# X14-Backplane.net
KiCad netlist of a schematic drawn in EAGLE
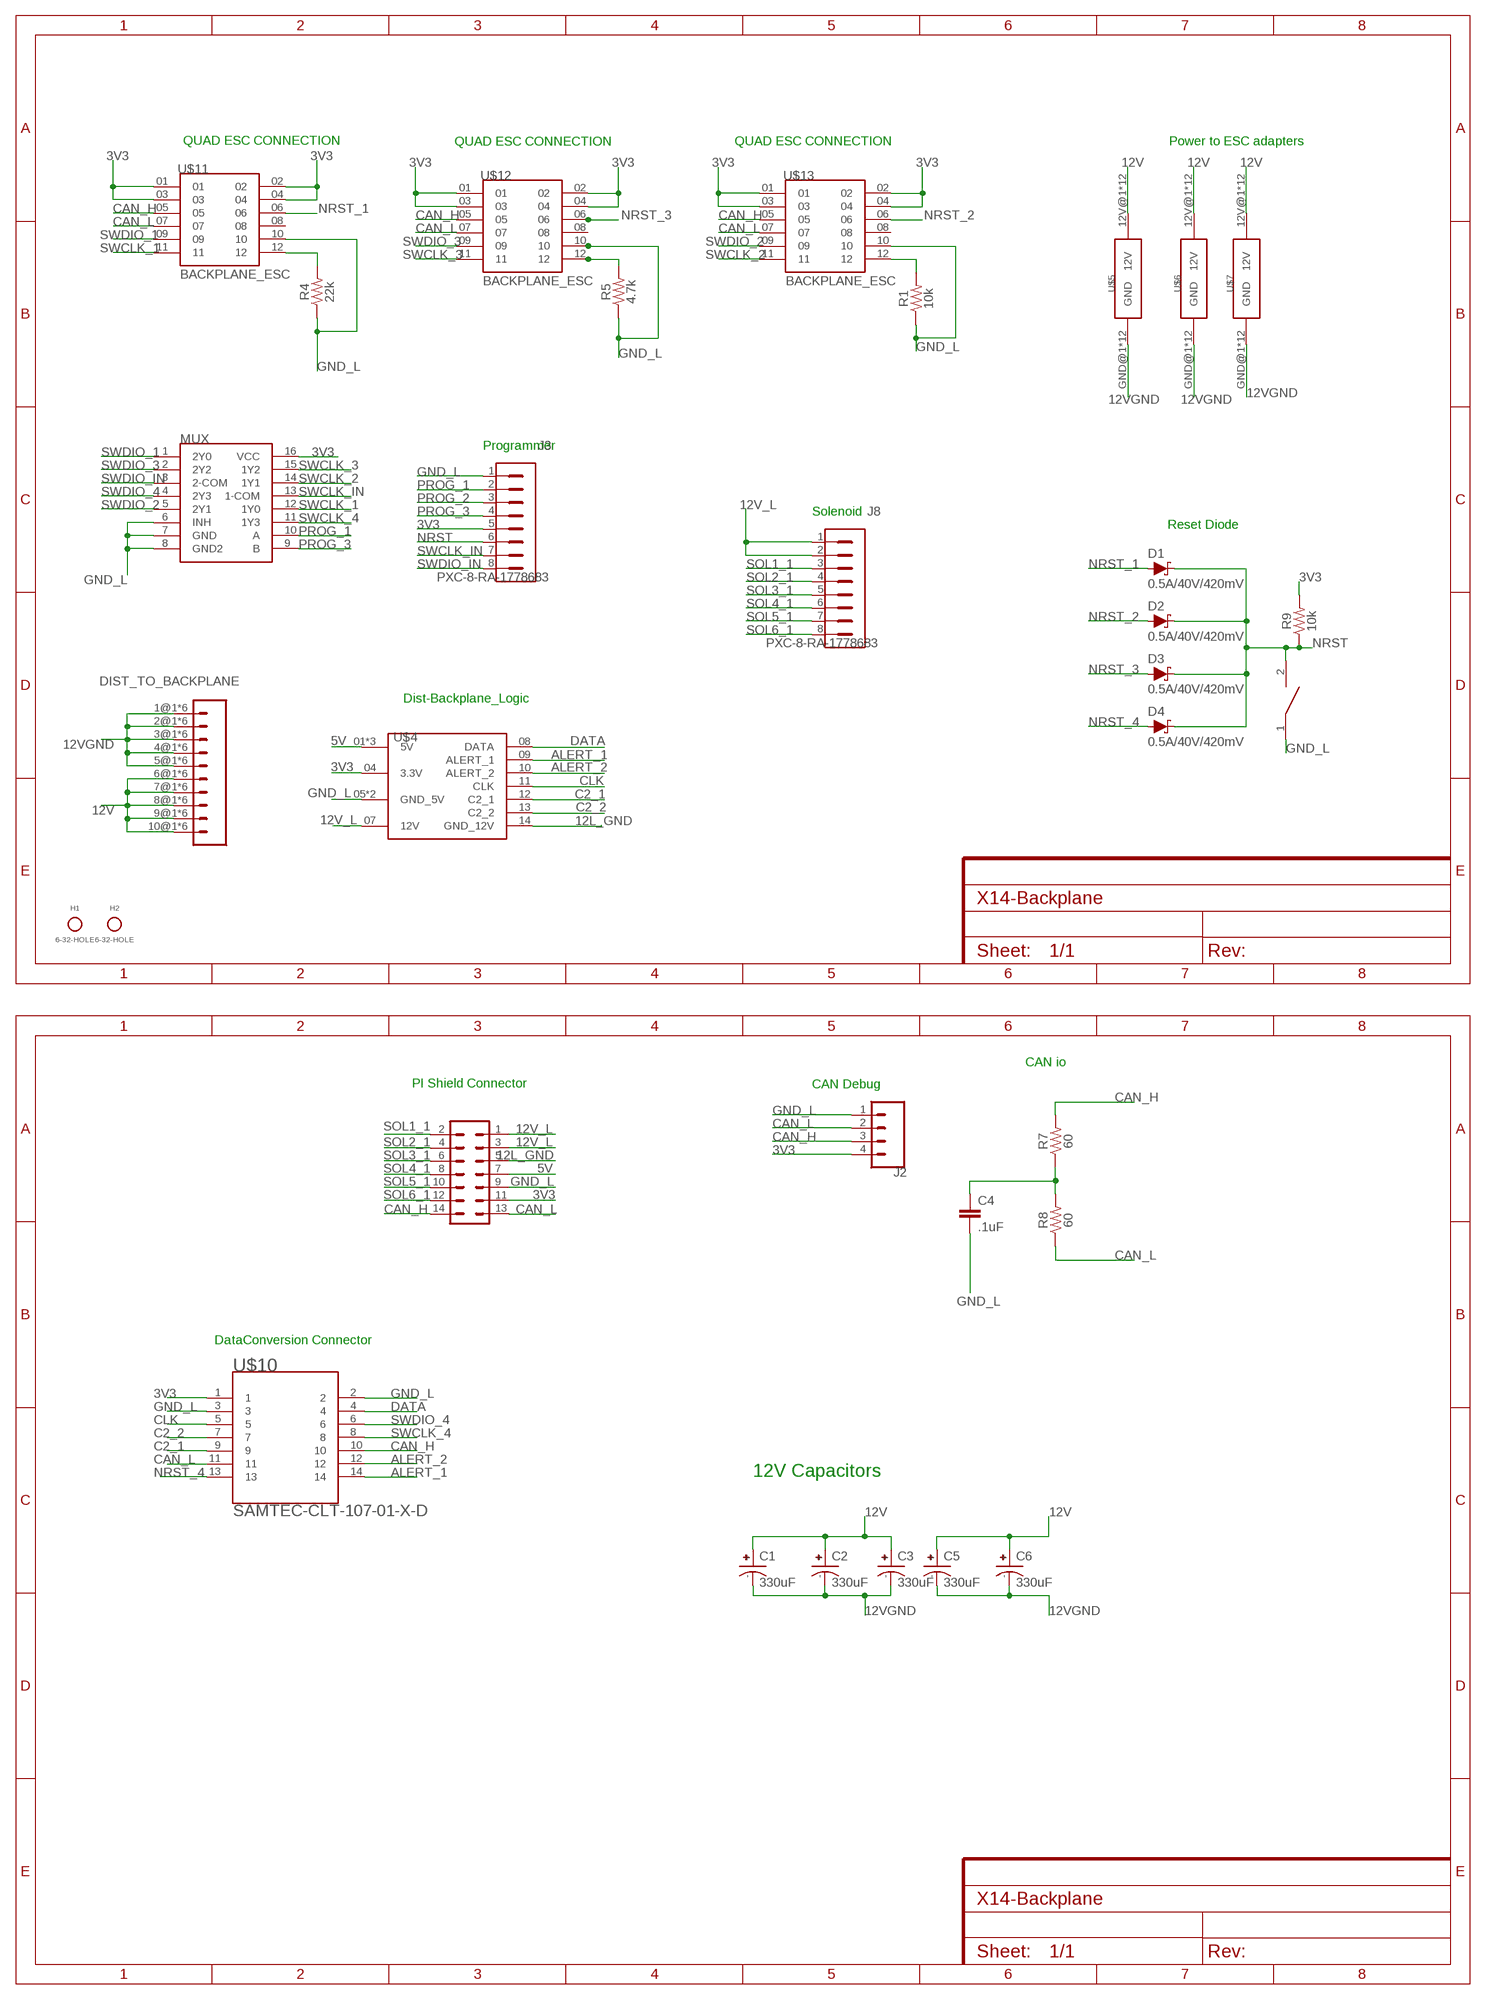
[diagram p0: schematic, sheet 1]

(export (version "E")
  (design (tool "Eeschema 10.0.6"))
  (components
    (comp (ref "C1")
      (value "330uF")
      (footprint "eagle-import:CAPAE1030X1050N")
      (fields
        (field (name "ARROW_PART_NUMBER") "UCM1H331MNL1GS")
        (field (name "MOUSER_PART_NUMBER") "647-UCM1H331MNL1GS")
      )
      (libsource (lib "eagle-import") (part "UCM1H331MNL1GS"))
    )
    (comp (ref "C2")
      (value "330uF")
      (footprint "eagle-import:CAPAE1030X1050N")
      (fields
        (field (name "ARROW_PART_NUMBER") "UCM1H331MNL1GS")
        (field (name "MOUSER_PART_NUMBER") "647-UCM1H331MNL1GS")
      )
      (libsource (lib "eagle-import") (part "UCM1H331MNL1GS"))
    )
    (comp (ref "C3")
      (value "330uF")
      (footprint "eagle-import:CAPAE1030X1050N")
      (fields
        (field (name "ARROW_PART_NUMBER") "UCM1H331MNL1GS")
        (field (name "MOUSER_PART_NUMBER") "647-UCM1H331MNL1GS")
      )
      (libsource (lib "eagle-import") (part "UCM1H331MNL1GS"))
    )
    (comp (ref "C4")
      (value ".1uF")
      (footprint "eagle-import:0603")
      (libsource (lib "eagle-import") (part "10NF-0603-50V-10%"))
    )
    (comp (ref "C5")
      (value "330uF")
      (footprint "eagle-import:CAPAE1030X1050N")
      (fields
        (field (name "ARROW_PART_NUMBER") "UCM1H331MNL1GS")
        (field (name "MOUSER_PART_NUMBER") "647-UCM1H331MNL1GS")
      )
      (libsource (lib "eagle-import") (part "UCM1H331MNL1GS"))
    )
    (comp (ref "C6")
      (value "330uF")
      (footprint "eagle-import:CAPAE1030X1050N")
      (fields
        (field (name "ARROW_PART_NUMBER") "UCM1H331MNL1GS")
        (field (name "MOUSER_PART_NUMBER") "647-UCM1H331MNL1GS")
      )
      (libsource (lib "eagle-import") (part "UCM1H331MNL1GS"))
    )
    (comp (ref "D1")
      (value "0.5A/40V/420mV")
      (footprint "eagle-import:SOD-323")
      (libsource (lib "eagle-import") (part "DIODE-SCHOTTKY-PMEG4005EJ"))
    )
    (comp (ref "D2")
      (value "0.5A/40V/420mV")
      (footprint "eagle-import:SOD-323")
      (libsource (lib "eagle-import") (part "DIODE-SCHOTTKY-PMEG4005EJ"))
    )
    (comp (ref "D3")
      (value "0.5A/40V/420mV")
      (footprint "eagle-import:SOD-323")
      (libsource (lib "eagle-import") (part "DIODE-SCHOTTKY-PMEG4005EJ"))
    )
    (comp (ref "D4")
      (value "0.5A/40V/420mV")
      (footprint "eagle-import:SOD-323")
      (libsource (lib "eagle-import") (part "DIODE-SCHOTTKY-PMEG4005EJ"))
    )
    (comp (ref "DIST_TO_BACKPLANE")
      (value "MPPT-10-01-01-L-RA-SD")
      (footprint "eagle-import:MPPT-10-01-01-L-RA-SD")
      (libsource (lib "eagle-import") (part "MPPT-10-01-01-L-RA-SD"))
    )
    (comp (ref "H1")
      (value "6-32-HOLE")
      (footprint "eagle-import:6-32-HOLE")
      (libsource (lib "eagle-import") (part "6-32-HOLE"))
    )
    (comp (ref "H2")
      (value "6-32-HOLE")
      (footprint "eagle-import:6-32-HOLE")
      (libsource (lib "eagle-import") (part "6-32-HOLE"))
    )
    (comp (ref "J2")
      (value "PXC-PTSM-04-RA-1778641")
      (footprint "eagle-import:PXC-PTSM-04-RA-1778641")
      (libsource (lib "eagle-import") (part "PXC-PTSM-04-RA-1778641"))
    )
    (comp (ref "J3")
      (value "PXC-8-RA-1778683")
      (footprint "eagle-import:PXC-8-RA-1778683")
      (libsource (lib "eagle-import") (part "PXC-8-RA-1778683"))
    )
    (comp (ref "J8")
      (value "PXC-8-RA-1778683")
      (footprint "eagle-import:PXC-8-RA-1778683")
      (libsource (lib "eagle-import") (part "PXC-8-RA-1778683"))
    )
    (comp (ref "MUX")
      (value "TI-SN74LV4052A")
      (footprint "eagle-import:SOIC-16")
      (libsource (lib "eagle-import") (part "TI-SN74LV4052A"))
    )
    (comp (ref "R1")
      (value "10k")
      (footprint "eagle-import:0603")
      (libsource (lib "eagle-import") (part "10KOHM-0603-1/10W-1%"))
    )
    (comp (ref "R4")
      (value "22k")
      (footprint "eagle-import:0603")
      (libsource (lib "eagle-import") (part "26.7KOHM0603-1/10W-1%"))
    )
    (comp (ref "R5")
      (value "4.7k")
      (footprint "eagle-import:0603")
      (libsource (lib "eagle-import") (part "1KOHM-0603-1/10W-1%"))
    )
    (comp (ref "R7")
      (value "60")
      (footprint "eagle-import:0603")
      (libsource (lib "eagle-import") (part "68.1KOHM-0603-1/10W-1%"))
    )
    (comp (ref "R8")
      (value "60")
      (footprint "eagle-import:0603")
      (libsource (lib "eagle-import") (part "68.1KOHM-0603-1/10W-1%"))
    )
    (comp (ref "R9")
      (value "10k")
      (footprint "eagle-import:0603")
      (libsource (lib "eagle-import") (part "10KOHM-0603-1/10W-1%"))
    )
    (comp (ref "U$4")
      (value "BACKPLANE-DISTRIBUTION")
      (footprint "eagle-import:SAMTEC_IPL1-107-01-X-D-K(B-D)")
      (libsource (lib "eagle-import") (part "BACKPLANE-DISTRIBUTION"))
    )
    (comp (ref "U$5")
      (value "BACKPLANE_ESC_ADAPTER_PWRBKP")
      (footprint "eagle-import:BACKPLANE_ESC_ADAPTER_BKP_PWR")
      (libsource (lib "eagle-import") (part "BACKPLANE_ESC_ADAPTER_PWRBKP"))
    )
    (comp (ref "U$6")
      (value "BACKPLANE_ESC_ADAPTER_PWRBKP")
      (footprint "eagle-import:BACKPLANE_ESC_ADAPTER_BKP_PWR")
      (libsource (lib "eagle-import") (part "BACKPLANE_ESC_ADAPTER_PWRBKP"))
    )
    (comp (ref "U$7")
      (value "BACKPLANE_ESC_ADAPTER_PWRBKP")
      (footprint "eagle-import:BACKPLANE_ESC_ADAPTER_BKP_PWR")
      (libsource (lib "eagle-import") (part "BACKPLANE_ESC_ADAPTER_PWRBKP"))
    )
    (comp (ref "U$8")
      (value "DISCRETECOMPONENTS_SWITCH")
      (footprint "eagle-import:DISCRETECOMPONENTS_SW_2512")
      (libsource (lib "eagle-import") (part "DISCRETECOMPONENTS_SWITCH"))
    )
    (comp (ref "U$9")
      (value "7X_CONN")
      (footprint "eagle-import:IPL7X2")
      (libsource (lib "eagle-import") (part "7X_CONN"))
    )
    (comp (ref "U$10")
      (value "BACKPLANE->DATACONV")
      (footprint "eagle-import:SAMTEC-CLT-107-01-X-D-BACKPLANE")
      (libsource (lib "eagle-import") (part "BACKPLANE-{gt}DATACONV"))
    )
    (comp (ref "U$11")
      (value "BACKPLANE_ESC")
      (footprint "eagle-import:SAMTEC_SQT-107-01-F-D")
      (libsource (lib "eagle-import") (part "BACKPLANE_ESC"))
    )
    (comp (ref "U$12")
      (value "BACKPLANE_ESC")
      (footprint "eagle-import:SAMTEC_SQT-107-01-F-D")
      (libsource (lib "eagle-import") (part "BACKPLANE_ESC"))
    )
    (comp (ref "U$13")
      (value "BACKPLANE_ESC")
      (footprint "eagle-import:SAMTEC_SQT-107-01-F-D")
      (libsource (lib "eagle-import") (part "BACKPLANE_ESC"))
    )
  )
  (nets
    (net (code "1") (name "/3V3") (class "Default")
      (node (ref "J2") (pin "4") (pinfunction "4_4") (pintype "passive"))
      (node (ref "J3") (pin "5") (pinfunction "5_5") (pintype "passive"))
      (node (ref "MUX") (pin "16") (pinfunction "VCC_16") (pintype "bidirectional"))
      (node (ref "R9") (pin "2") (pinfunction "2_2") (pintype "passive"))
      (node (ref "U$10") (pin "1") (pinfunction "1_1") (pintype "passive"))
      (node (ref "U$11") (pin "01") (pinfunction "01_01") (pintype "passive"))
      (node (ref "U$11") (pin "02") (pinfunction "02_02") (pintype "passive"))
      (node (ref "U$11") (pin "03") (pinfunction "03_03") (pintype "passive"))
      (node (ref "U$11") (pin "04") (pinfunction "04_04") (pintype "passive"))
      (node (ref "U$12") (pin "01") (pinfunction "01_01") (pintype "passive"))
      (node (ref "U$12") (pin "02") (pinfunction "02_02") (pintype "passive"))
      (node (ref "U$12") (pin "03") (pinfunction "03_03") (pintype "passive"))
      (node (ref "U$12") (pin "04") (pinfunction "04_04") (pintype "passive"))
      (node (ref "U$13") (pin "01") (pinfunction "01_01") (pintype "passive"))
      (node (ref "U$13") (pin "02") (pinfunction "02_02") (pintype "passive"))
      (node (ref "U$13") (pin "03") (pinfunction "03_03") (pintype "passive"))
      (node (ref "U$13") (pin "04") (pinfunction "04_04") (pintype "passive"))
      (node (ref "U$4") (pin "04") (pinfunction "3.3V_04") (pintype "passive"))
      (node (ref "U$9") (pin "11") (pinfunction "24_11") (pintype "passive"))
    )
    (net (code "2") (name "/5V") (class "Default")
      (node (ref "U$4") (pin "01") (pinfunction "5V_01") (pintype "passive"))
      (node (ref "U$4") (pin "02") (pinfunction "5V_02") (pintype "passive"))
      (node (ref "U$4") (pin "03") (pinfunction "5V_03") (pintype "passive"))
      (node (ref "U$9") (pin "7") (pinfunction "20_7") (pintype "passive"))
    )
    (net (code "3") (name "/12L_GND") (class "Default")
      (node (ref "U$4") (pin "14") (pinfunction "GND_12V_14") (pintype "passive"))
      (node (ref "U$9") (pin "5") (pinfunction "18_5") (pintype "passive"))
    )
    (net (code "4") (name "/12V") (class "Default")
      (node (ref "C1") (pin "+") (pinfunction "+_+") (pintype "bidirectional"))
      (node (ref "C2") (pin "+") (pinfunction "+_+") (pintype "bidirectional"))
      (node (ref "C3") (pin "+") (pinfunction "+_+") (pintype "bidirectional"))
      (node (ref "C5") (pin "+") (pinfunction "+_+") (pintype "bidirectional"))
      (node (ref "C6") (pin "+") (pinfunction "+_+") (pintype "bidirectional"))
      (node (ref "DIST_TO_BACKPLANE") (pin "10@1") (pinfunction "10_10@1") (pintype "passive"))
      (node (ref "DIST_TO_BACKPLANE") (pin "10@2") (pinfunction "10_10@2") (pintype "passive"))
      (node (ref "DIST_TO_BACKPLANE") (pin "10@3") (pinfunction "10_10@3") (pintype "passive"))
      (node (ref "DIST_TO_BACKPLANE") (pin "10@4") (pinfunction "10_10@4") (pintype "passive"))
      (node (ref "DIST_TO_BACKPLANE") (pin "10@5") (pinfunction "10_10@5") (pintype "passive"))
      (node (ref "DIST_TO_BACKPLANE") (pin "10@6") (pinfunction "10_10@6") (pintype "passive"))
      (node (ref "DIST_TO_BACKPLANE") (pin "6@1") (pinfunction "6_6@1") (pintype "passive"))
      (node (ref "DIST_TO_BACKPLANE") (pin "6@2") (pinfunction "6_6@2") (pintype "passive"))
      (node (ref "DIST_TO_BACKPLANE") (pin "6@3") (pinfunction "6_6@3") (pintype "passive"))
      (node (ref "DIST_TO_BACKPLANE") (pin "6@4") (pinfunction "6_6@4") (pintype "passive"))
      (node (ref "DIST_TO_BACKPLANE") (pin "6@5") (pinfunction "6_6@5") (pintype "passive"))
      (node (ref "DIST_TO_BACKPLANE") (pin "6@6") (pinfunction "6_6@6") (pintype "passive"))
      (node (ref "DIST_TO_BACKPLANE") (pin "7@1") (pinfunction "7_7@1") (pintype "passive"))
      (node (ref "DIST_TO_BACKPLANE") (pin "7@2") (pinfunction "7_7@2") (pintype "passive"))
      (node (ref "DIST_TO_BACKPLANE") (pin "7@3") (pinfunction "7_7@3") (pintype "passive"))
      (node (ref "DIST_TO_BACKPLANE") (pin "7@4") (pinfunction "7_7@4") (pintype "passive"))
      (node (ref "DIST_TO_BACKPLANE") (pin "7@5") (pinfunction "7_7@5") (pintype "passive"))
      (node (ref "DIST_TO_BACKPLANE") (pin "7@6") (pinfunction "7_7@6") (pintype "passive"))
      (node (ref "DIST_TO_BACKPLANE") (pin "8@1") (pinfunction "8_8@1") (pintype "passive"))
      (node (ref "DIST_TO_BACKPLANE") (pin "8@2") (pinfunction "8_8@2") (pintype "passive"))
      (node (ref "DIST_TO_BACKPLANE") (pin "8@3") (pinfunction "8_8@3") (pintype "passive"))
      (node (ref "DIST_TO_BACKPLANE") (pin "8@4") (pinfunction "8_8@4") (pintype "passive"))
      (node (ref "DIST_TO_BACKPLANE") (pin "8@5") (pinfunction "8_8@5") (pintype "passive"))
      (node (ref "DIST_TO_BACKPLANE") (pin "8@6") (pinfunction "8_8@6") (pintype "passive"))
      (node (ref "DIST_TO_BACKPLANE") (pin "9@1") (pinfunction "9_9@1") (pintype "passive"))
      (node (ref "DIST_TO_BACKPLANE") (pin "9@2") (pinfunction "9_9@2") (pintype "passive"))
      (node (ref "DIST_TO_BACKPLANE") (pin "9@3") (pinfunction "9_9@3") (pintype "passive"))
      (node (ref "DIST_TO_BACKPLANE") (pin "9@4") (pinfunction "9_9@4") (pintype "passive"))
      (node (ref "DIST_TO_BACKPLANE") (pin "9@5") (pinfunction "9_9@5") (pintype "passive"))
      (node (ref "DIST_TO_BACKPLANE") (pin "9@6") (pinfunction "9_9@6") (pintype "passive"))
      (node (ref "U$5") (pin "12V@1") (pinfunction "12V_12V@1") (pintype "bidirectional"))
      (node (ref "U$5") (pin "12V@10") (pinfunction "12V_12V@10") (pintype "bidirectional"))
      (node (ref "U$5") (pin "12V@11") (pinfunction "12V_12V@11") (pintype "bidirectional"))
      (node (ref "U$5") (pin "12V@12") (pinfunction "12V_12V@12") (pintype "bidirectional"))
      (node (ref "U$5") (pin "12V@2") (pinfunction "12V_12V@2") (pintype "bidirectional"))
      (node (ref "U$5") (pin "12V@3") (pinfunction "12V_12V@3") (pintype "bidirectional"))
      (node (ref "U$5") (pin "12V@4") (pinfunction "12V_12V@4") (pintype "bidirectional"))
      (node (ref "U$5") (pin "12V@5") (pinfunction "12V_12V@5") (pintype "bidirectional"))
      (node (ref "U$5") (pin "12V@6") (pinfunction "12V_12V@6") (pintype "bidirectional"))
      (node (ref "U$5") (pin "12V@7") (pinfunction "12V_12V@7") (pintype "bidirectional"))
      (node (ref "U$5") (pin "12V@8") (pinfunction "12V_12V@8") (pintype "bidirectional"))
      (node (ref "U$5") (pin "12V@9") (pinfunction "12V_12V@9") (pintype "bidirectional"))
      (node (ref "U$6") (pin "12V@1") (pinfunction "12V_12V@1") (pintype "bidirectional"))
      (node (ref "U$6") (pin "12V@10") (pinfunction "12V_12V@10") (pintype "bidirectional"))
      (node (ref "U$6") (pin "12V@11") (pinfunction "12V_12V@11") (pintype "bidirectional"))
      (node (ref "U$6") (pin "12V@12") (pinfunction "12V_12V@12") (pintype "bidirectional"))
      (node (ref "U$6") (pin "12V@2") (pinfunction "12V_12V@2") (pintype "bidirectional"))
      (node (ref "U$6") (pin "12V@3") (pinfunction "12V_12V@3") (pintype "bidirectional"))
      (node (ref "U$6") (pin "12V@4") (pinfunction "12V_12V@4") (pintype "bidirectional"))
      (node (ref "U$6") (pin "12V@5") (pinfunction "12V_12V@5") (pintype "bidirectional"))
      (node (ref "U$6") (pin "12V@6") (pinfunction "12V_12V@6") (pintype "bidirectional"))
      (node (ref "U$6") (pin "12V@7") (pinfunction "12V_12V@7") (pintype "bidirectional"))
      (node (ref "U$6") (pin "12V@8") (pinfunction "12V_12V@8") (pintype "bidirectional"))
      (node (ref "U$6") (pin "12V@9") (pinfunction "12V_12V@9") (pintype "bidirectional"))
      (node (ref "U$7") (pin "12V@1") (pinfunction "12V_12V@1") (pintype "bidirectional"))
      (node (ref "U$7") (pin "12V@10") (pinfunction "12V_12V@10") (pintype "bidirectional"))
      (node (ref "U$7") (pin "12V@11") (pinfunction "12V_12V@11") (pintype "bidirectional"))
      (node (ref "U$7") (pin "12V@12") (pinfunction "12V_12V@12") (pintype "bidirectional"))
      (node (ref "U$7") (pin "12V@2") (pinfunction "12V_12V@2") (pintype "bidirectional"))
      (node (ref "U$7") (pin "12V@3") (pinfunction "12V_12V@3") (pintype "bidirectional"))
      (node (ref "U$7") (pin "12V@4") (pinfunction "12V_12V@4") (pintype "bidirectional"))
      (node (ref "U$7") (pin "12V@5") (pinfunction "12V_12V@5") (pintype "bidirectional"))
      (node (ref "U$7") (pin "12V@6") (pinfunction "12V_12V@6") (pintype "bidirectional"))
      (node (ref "U$7") (pin "12V@7") (pinfunction "12V_12V@7") (pintype "bidirectional"))
      (node (ref "U$7") (pin "12V@8") (pinfunction "12V_12V@8") (pintype "bidirectional"))
      (node (ref "U$7") (pin "12V@9") (pinfunction "12V_12V@9") (pintype "bidirectional"))
    )
    (net (code "5") (name "/12VGND") (class "Default")
      (node (ref "C1") (pin "-") (pinfunction "-_-") (pintype "bidirectional"))
      (node (ref "C2") (pin "-") (pinfunction "-_-") (pintype "bidirectional"))
      (node (ref "C3") (pin "-") (pinfunction "-_-") (pintype "bidirectional"))
      (node (ref "C5") (pin "-") (pinfunction "-_-") (pintype "bidirectional"))
      (node (ref "C6") (pin "-") (pinfunction "-_-") (pintype "bidirectional"))
      (node (ref "DIST_TO_BACKPLANE") (pin "1@1") (pinfunction "1_1@1") (pintype "passive"))
      (node (ref "DIST_TO_BACKPLANE") (pin "1@2") (pinfunction "1_1@2") (pintype "passive"))
      (node (ref "DIST_TO_BACKPLANE") (pin "1@3") (pinfunction "1_1@3") (pintype "passive"))
      (node (ref "DIST_TO_BACKPLANE") (pin "1@4") (pinfunction "1_1@4") (pintype "passive"))
      (node (ref "DIST_TO_BACKPLANE") (pin "1@5") (pinfunction "1_1@5") (pintype "passive"))
      (node (ref "DIST_TO_BACKPLANE") (pin "1@6") (pinfunction "1_1@6") (pintype "passive"))
      (node (ref "DIST_TO_BACKPLANE") (pin "2@1") (pinfunction "2_2@1") (pintype "passive"))
      (node (ref "DIST_TO_BACKPLANE") (pin "2@2") (pinfunction "2_2@2") (pintype "passive"))
      (node (ref "DIST_TO_BACKPLANE") (pin "2@3") (pinfunction "2_2@3") (pintype "passive"))
      (node (ref "DIST_TO_BACKPLANE") (pin "2@4") (pinfunction "2_2@4") (pintype "passive"))
      (node (ref "DIST_TO_BACKPLANE") (pin "2@5") (pinfunction "2_2@5") (pintype "passive"))
      (node (ref "DIST_TO_BACKPLANE") (pin "2@6") (pinfunction "2_2@6") (pintype "passive"))
      (node (ref "DIST_TO_BACKPLANE") (pin "3@1") (pinfunction "3_3@1") (pintype "passive"))
      (node (ref "DIST_TO_BACKPLANE") (pin "3@2") (pinfunction "3_3@2") (pintype "passive"))
      (node (ref "DIST_TO_BACKPLANE") (pin "3@3") (pinfunction "3_3@3") (pintype "passive"))
      (node (ref "DIST_TO_BACKPLANE") (pin "3@4") (pinfunction "3_3@4") (pintype "passive"))
      (node (ref "DIST_TO_BACKPLANE") (pin "3@5") (pinfunction "3_3@5") (pintype "passive"))
      (node (ref "DIST_TO_BACKPLANE") (pin "3@6") (pinfunction "3_3@6") (pintype "passive"))
      (node (ref "DIST_TO_BACKPLANE") (pin "4@1") (pinfunction "4_4@1") (pintype "passive"))
      (node (ref "DIST_TO_BACKPLANE") (pin "4@2") (pinfunction "4_4@2") (pintype "passive"))
      (node (ref "DIST_TO_BACKPLANE") (pin "4@3") (pinfunction "4_4@3") (pintype "passive"))
      (node (ref "DIST_TO_BACKPLANE") (pin "4@4") (pinfunction "4_4@4") (pintype "passive"))
      (node (ref "DIST_TO_BACKPLANE") (pin "4@5") (pinfunction "4_4@5") (pintype "passive"))
      (node (ref "DIST_TO_BACKPLANE") (pin "4@6") (pinfunction "4_4@6") (pintype "passive"))
      (node (ref "DIST_TO_BACKPLANE") (pin "5@1") (pinfunction "5_5@1") (pintype "passive"))
      (node (ref "DIST_TO_BACKPLANE") (pin "5@2") (pinfunction "5_5@2") (pintype "passive"))
      (node (ref "DIST_TO_BACKPLANE") (pin "5@3") (pinfunction "5_5@3") (pintype "passive"))
      (node (ref "DIST_TO_BACKPLANE") (pin "5@4") (pinfunction "5_5@4") (pintype "passive"))
      (node (ref "DIST_TO_BACKPLANE") (pin "5@5") (pinfunction "5_5@5") (pintype "passive"))
      (node (ref "DIST_TO_BACKPLANE") (pin "5@6") (pinfunction "5_5@6") (pintype "passive"))
      (node (ref "U$5") (pin "GND@1") (pinfunction "GND_GND@1") (pintype "bidirectional"))
      (node (ref "U$5") (pin "GND@10") (pinfunction "GND_GND@10") (pintype "bidirectional"))
      (node (ref "U$5") (pin "GND@11") (pinfunction "GND_GND@11") (pintype "bidirectional"))
      (node (ref "U$5") (pin "GND@12") (pinfunction "GND_GND@12") (pintype "bidirectional"))
      (node (ref "U$5") (pin "GND@2") (pinfunction "GND_GND@2") (pintype "bidirectional"))
      (node (ref "U$5") (pin "GND@3") (pinfunction "GND_GND@3") (pintype "bidirectional"))
      (node (ref "U$5") (pin "GND@4") (pinfunction "GND_GND@4") (pintype "bidirectional"))
      (node (ref "U$5") (pin "GND@5") (pinfunction "GND_GND@5") (pintype "bidirectional"))
      (node (ref "U$5") (pin "GND@6") (pinfunction "GND_GND@6") (pintype "bidirectional"))
      (node (ref "U$5") (pin "GND@7") (pinfunction "GND_GND@7") (pintype "bidirectional"))
      (node (ref "U$5") (pin "GND@8") (pinfunction "GND_GND@8") (pintype "bidirectional"))
      (node (ref "U$5") (pin "GND@9") (pinfunction "GND_GND@9") (pintype "bidirectional"))
      (node (ref "U$6") (pin "GND@1") (pinfunction "GND_GND@1") (pintype "bidirectional"))
      (node (ref "U$6") (pin "GND@10") (pinfunction "GND_GND@10") (pintype "bidirectional"))
      (node (ref "U$6") (pin "GND@11") (pinfunction "GND_GND@11") (pintype "bidirectional"))
      (node (ref "U$6") (pin "GND@12") (pinfunction "GND_GND@12") (pintype "bidirectional"))
      (node (ref "U$6") (pin "GND@2") (pinfunction "GND_GND@2") (pintype "bidirectional"))
      (node (ref "U$6") (pin "GND@3") (pinfunction "GND_GND@3") (pintype "bidirectional"))
      (node (ref "U$6") (pin "GND@4") (pinfunction "GND_GND@4") (pintype "bidirectional"))
      (node (ref "U$6") (pin "GND@5") (pinfunction "GND_GND@5") (pintype "bidirectional"))
      (node (ref "U$6") (pin "GND@6") (pinfunction "GND_GND@6") (pintype "bidirectional"))
      (node (ref "U$6") (pin "GND@7") (pinfunction "GND_GND@7") (pintype "bidirectional"))
      (node (ref "U$6") (pin "GND@8") (pinfunction "GND_GND@8") (pintype "bidirectional"))
      (node (ref "U$6") (pin "GND@9") (pinfunction "GND_GND@9") (pintype "bidirectional"))
      (node (ref "U$7") (pin "GND@1") (pinfunction "GND_GND@1") (pintype "bidirectional"))
      (node (ref "U$7") (pin "GND@10") (pinfunction "GND_GND@10") (pintype "bidirectional"))
      (node (ref "U$7") (pin "GND@11") (pinfunction "GND_GND@11") (pintype "bidirectional"))
      (node (ref "U$7") (pin "GND@12") (pinfunction "GND_GND@12") (pintype "bidirectional"))
      (node (ref "U$7") (pin "GND@2") (pinfunction "GND_GND@2") (pintype "bidirectional"))
      (node (ref "U$7") (pin "GND@3") (pinfunction "GND_GND@3") (pintype "bidirectional"))
      (node (ref "U$7") (pin "GND@4") (pinfunction "GND_GND@4") (pintype "bidirectional"))
      (node (ref "U$7") (pin "GND@5") (pinfunction "GND_GND@5") (pintype "bidirectional"))
      (node (ref "U$7") (pin "GND@6") (pinfunction "GND_GND@6") (pintype "bidirectional"))
      (node (ref "U$7") (pin "GND@7") (pinfunction "GND_GND@7") (pintype "bidirectional"))
      (node (ref "U$7") (pin "GND@8") (pinfunction "GND_GND@8") (pintype "bidirectional"))
      (node (ref "U$7") (pin "GND@9") (pinfunction "GND_GND@9") (pintype "bidirectional"))
    )
    (net (code "6") (name "/12V_L") (class "Default")
      (node (ref "J8") (pin "1") (pinfunction "1_1") (pintype "passive"))
      (node (ref "J8") (pin "2") (pinfunction "2_2") (pintype "passive"))
      (node (ref "U$4") (pin "07") (pinfunction "12V_07") (pintype "passive"))
      (node (ref "U$9") (pin "1") (pinfunction "14_1") (pintype "passive"))
      (node (ref "U$9") (pin "3") (pinfunction "16_3") (pintype "passive"))
    )
    (net (code "7") (name "/ALERT_1") (class "Default")
      (node (ref "U$10") (pin "14") (pinfunction "14_14") (pintype "passive"))
      (node (ref "U$4") (pin "09") (pinfunction "ALERT_1_09") (pintype "passive"))
    )
    (net (code "8") (name "/ALERT_2") (class "Default")
      (node (ref "U$10") (pin "12") (pinfunction "12_12") (pintype "passive"))
      (node (ref "U$4") (pin "10") (pinfunction "ALERT_2_10") (pintype "passive"))
    )
    (net (code "9") (name "/C2_1") (class "Default")
      (node (ref "U$10") (pin "9") (pinfunction "9_9") (pintype "passive"))
      (node (ref "U$4") (pin "12") (pinfunction "C2_1_12") (pintype "passive"))
    )
    (net (code "10") (name "/C2_2") (class "Default")
      (node (ref "U$10") (pin "7") (pinfunction "7_7") (pintype "passive"))
      (node (ref "U$4") (pin "13") (pinfunction "C2_2_13") (pintype "passive"))
    )
    (net (code "11") (name "/CAN_H") (class "Default")
      (node (ref "J2") (pin "3") (pinfunction "3_3") (pintype "passive"))
      (node (ref "R7") (pin "2") (pinfunction "2_2") (pintype "passive"))
      (node (ref "U$10") (pin "10") (pinfunction "10_10") (pintype "passive"))
      (node (ref "U$11") (pin "05") (pinfunction "05_05") (pintype "passive"))
      (node (ref "U$12") (pin "05") (pinfunction "05_05") (pintype "passive"))
      (node (ref "U$13") (pin "05") (pinfunction "05_05") (pintype "passive"))
      (node (ref "U$9") (pin "14") (pinfunction "2_14") (pintype "passive"))
    )
    (net (code "12") (name "/CAN_L") (class "Default")
      (node (ref "J2") (pin "2") (pinfunction "2_2") (pintype "passive"))
      (node (ref "R8") (pin "1") (pinfunction "1_1") (pintype "passive"))
      (node (ref "U$10") (pin "11") (pinfunction "11_11") (pintype "passive"))
      (node (ref "U$11") (pin "07") (pinfunction "07_07") (pintype "passive"))
      (node (ref "U$12") (pin "07") (pinfunction "07_07") (pintype "passive"))
      (node (ref "U$13") (pin "07") (pinfunction "07_07") (pintype "passive"))
      (node (ref "U$9") (pin "13") (pinfunction "1_13") (pintype "passive"))
    )
    (net (code "13") (name "/CLK") (class "Default")
      (node (ref "U$10") (pin "5") (pinfunction "5_5") (pintype "passive"))
      (node (ref "U$4") (pin "11") (pinfunction "CLK_11") (pintype "passive"))
    )
    (net (code "14") (name "/DATA") (class "Default")
      (node (ref "U$10") (pin "4") (pinfunction "4_4") (pintype "passive"))
      (node (ref "U$4") (pin "08") (pinfunction "DATA_08") (pintype "passive"))
    )
    (net (code "15") (name "/GND_L") (class "Default")
      (node (ref "C4") (pin "2") (pinfunction "2_2") (pintype "passive"))
      (node (ref "J2") (pin "1") (pinfunction "1_1") (pintype "passive"))
      (node (ref "J3") (pin "1") (pinfunction "1_1") (pintype "passive"))
      (node (ref "MUX") (pin "6") (pinfunction "INH_6") (pintype "bidirectional"))
      (node (ref "MUX") (pin "7") (pinfunction "GND_7") (pintype "bidirectional"))
      (node (ref "MUX") (pin "8") (pinfunction "GND2_8") (pintype "bidirectional"))
      (node (ref "R1") (pin "1") (pinfunction "1_1") (pintype "passive"))
      (node (ref "R4") (pin "1") (pinfunction "1_1") (pintype "passive"))
      (node (ref "R5") (pin "1") (pinfunction "1_1") (pintype "passive"))
      (node (ref "U$10") (pin "2") (pinfunction "2_2") (pintype "passive"))
      (node (ref "U$10") (pin "3") (pinfunction "3_3") (pintype "passive"))
      (node (ref "U$11") (pin "10") (pinfunction "10_10") (pintype "passive"))
      (node (ref "U$12") (pin "10") (pinfunction "10_10") (pintype "passive"))
      (node (ref "U$13") (pin "10") (pinfunction "10_10") (pintype "passive"))
      (node (ref "U$4") (pin "05") (pinfunction "GND_5V_05") (pintype "passive"))
      (node (ref "U$4") (pin "06") (pinfunction "GND_5V_06") (pintype "passive"))
      (node (ref "U$8") (pin "1") (pinfunction "P$1_1") (pintype "bidirectional"))
      (node (ref "U$9") (pin "9") (pinfunction "22_9") (pintype "passive"))
    )
    (net (code "16") (name "/NRST") (class "Default")
      (node (ref "D1") (pin "C") (pinfunction "C_C") (pintype "passive"))
      (node (ref "D2") (pin "C") (pinfunction "C_C") (pintype "passive"))
      (node (ref "D3") (pin "C") (pinfunction "C_C") (pintype "passive"))
      (node (ref "D4") (pin "C") (pinfunction "C_C") (pintype "passive"))
      (node (ref "J3") (pin "6") (pinfunction "6_6") (pintype "passive"))
      (node (ref "R9") (pin "1") (pinfunction "1_1") (pintype "passive"))
      (node (ref "U$8") (pin "2") (pinfunction "P$2_2") (pintype "bidirectional"))
    )
    (net (code "17") (name "/NRST_1") (class "Default")
      (node (ref "D1") (pin "A") (pinfunction "A_A") (pintype "passive"))
      (node (ref "U$11") (pin "06") (pinfunction "06_06") (pintype "passive"))
    )
    (net (code "18") (name "/NRST_2") (class "Default")
      (node (ref "D2") (pin "A") (pinfunction "A_A") (pintype "passive"))
      (node (ref "U$13") (pin "06") (pinfunction "06_06") (pintype "passive"))
    )
    (net (code "19") (name "/NRST_3") (class "Default")
      (node (ref "D3") (pin "A") (pinfunction "A_A") (pintype "passive"))
      (node (ref "U$12") (pin "06") (pinfunction "06_06") (pintype "passive"))
    )
    (net (code "20") (name "/NRST_4") (class "Default")
      (node (ref "D4") (pin "A") (pinfunction "A_A") (pintype "passive"))
      (node (ref "U$10") (pin "13") (pinfunction "13_13") (pintype "passive"))
    )
    (net (code "21") (name "/PROG_1") (class "Default")
      (node (ref "J3") (pin "2") (pinfunction "2_2") (pintype "passive"))
      (node (ref "MUX") (pin "10") (pinfunction "A_10") (pintype "bidirectional"))
    )
    (net (code "22") (name "/PROG_2") (class "Default")
      (node (ref "J3") (pin "3") (pinfunction "3_3") (pintype "passive"))
    )
    (net (code "23") (name "/PROG_3") (class "Default")
      (node (ref "J3") (pin "4") (pinfunction "4_4") (pintype "passive"))
      (node (ref "MUX") (pin "9") (pinfunction "B_9") (pintype "bidirectional"))
    )
    (net (code "24") (name "/SOL1_1") (class "Default")
      (node (ref "J8") (pin "3") (pinfunction "3_3") (pintype "passive"))
      (node (ref "U$9") (pin "2") (pinfunction "13_2") (pintype "passive"))
    )
    (net (code "25") (name "/SOL2_1") (class "Default")
      (node (ref "J8") (pin "4") (pinfunction "4_4") (pintype "passive"))
      (node (ref "U$9") (pin "4") (pinfunction "15_4") (pintype "passive"))
    )
    (net (code "26") (name "/SOL3_1") (class "Default")
      (node (ref "J8") (pin "5") (pinfunction "5_5") (pintype "passive"))
      (node (ref "U$9") (pin "6") (pinfunction "17_6") (pintype "passive"))
    )
    (net (code "27") (name "/SOL4_1") (class "Default")
      (node (ref "J8") (pin "6") (pinfunction "6_6") (pintype "passive"))
      (node (ref "U$9") (pin "8") (pinfunction "19_8") (pintype "passive"))
    )
    (net (code "28") (name "/SOL5_1") (class "Default")
      (node (ref "J8") (pin "7") (pinfunction "7_7") (pintype "passive"))
      (node (ref "U$9") (pin "10") (pinfunction "21_10") (pintype "passive"))
    )
    (net (code "29") (name "/SOL6_1") (class "Default")
      (node (ref "J8") (pin "8") (pinfunction "8_8") (pintype "passive"))
      (node (ref "U$9") (pin "12") (pinfunction "23_12") (pintype "passive"))
    )
    (net (code "30") (name "/SWCLK_1") (class "Default")
      (node (ref "MUX") (pin "12") (pinfunction "1Y0_12") (pintype "bidirectional"))
      (node (ref "U$11") (pin "11") (pinfunction "11_11") (pintype "passive"))
    )
    (net (code "31") (name "/SWCLK_2") (class "Default")
      (node (ref "MUX") (pin "14") (pinfunction "1Y1_14") (pintype "bidirectional"))
      (node (ref "U$13") (pin "11") (pinfunction "11_11") (pintype "passive"))
    )
    (net (code "32") (name "/SWCLK_3") (class "Default")
      (node (ref "MUX") (pin "15") (pinfunction "1Y2_15") (pintype "bidirectional"))
      (node (ref "U$12") (pin "11") (pinfunction "11_11") (pintype "passive"))
    )
    (net (code "33") (name "/SWCLK_4") (class "Default")
      (node (ref "MUX") (pin "11") (pinfunction "1Y3_11") (pintype "bidirectional"))
      (node (ref "U$10") (pin "8") (pinfunction "8_8") (pintype "passive"))
    )
    (net (code "34") (name "/SWCLK_IN") (class "Default")
      (node (ref "J3") (pin "7") (pinfunction "7_7") (pintype "passive"))
      (node (ref "MUX") (pin "13") (pinfunction "1-COM_13") (pintype "bidirectional"))
    )
    (net (code "35") (name "/SWDIO_1") (class "Default")
      (node (ref "MUX") (pin "1") (pinfunction "2Y0_1") (pintype "bidirectional"))
      (node (ref "U$11") (pin "09") (pinfunction "09_09") (pintype "passive"))
    )
    (net (code "36") (name "/SWDIO_2") (class "Default")
      (node (ref "MUX") (pin "5") (pinfunction "2Y1_5") (pintype "bidirectional"))
      (node (ref "U$13") (pin "09") (pinfunction "09_09") (pintype "passive"))
    )
    (net (code "37") (name "/SWDIO_3") (class "Default")
      (node (ref "MUX") (pin "2") (pinfunction "2Y2_2") (pintype "bidirectional"))
      (node (ref "U$12") (pin "09") (pinfunction "09_09") (pintype "passive"))
    )
    (net (code "38") (name "/SWDIO_4") (class "Default")
      (node (ref "MUX") (pin "4") (pinfunction "2Y3_4") (pintype "bidirectional"))
      (node (ref "U$10") (pin "6") (pinfunction "6_6") (pintype "passive"))
    )
    (net (code "39") (name "/SWDIO_IN") (class "Default")
      (node (ref "J3") (pin "8") (pinfunction "8_8") (pintype "passive"))
      (node (ref "MUX") (pin "3") (pinfunction "2-COM_3") (pintype "bidirectional"))
    )
    (net (code "40") (name "Net-(C4-Pad1)") (class "Default")
      (node (ref "C4") (pin "1") (pinfunction "1_1") (pintype "passive"))
      (node (ref "R7") (pin "1") (pinfunction "1_1") (pintype "passive"))
      (node (ref "R8") (pin "2") (pinfunction "2_2") (pintype "passive"))
    )
    (net (code "41") (name "Net-(R1-Pad2)") (class "Default")
      (node (ref "R1") (pin "2") (pinfunction "2_2") (pintype "passive"))
      (node (ref "U$13") (pin "12") (pinfunction "12_12") (pintype "passive"))
    )
    (net (code "42") (name "Net-(R4-Pad2)") (class "Default")
      (node (ref "R4") (pin "2") (pinfunction "2_2") (pintype "passive"))
      (node (ref "U$11") (pin "12") (pinfunction "12_12") (pintype "passive"))
    )
    (net (code "43") (name "Net-(R5-Pad2)") (class "Default")
      (node (ref "R5") (pin "2") (pinfunction "2_2") (pintype "passive"))
      (node (ref "U$12") (pin "12") (pinfunction "12_12") (pintype "passive"))
    )
    (net (code "44") (name "unconnected-(U$11-Pad08)") (class "Default")
      (node (ref "U$11") (pin "08") (pinfunction "08_08") (pintype "passive"))
    )
    (net (code "45") (name "unconnected-(U$12-Pad08)") (class "Default")
      (node (ref "U$12") (pin "08") (pinfunction "08_08") (pintype "passive"))
    )
    (net (code "46") (name "unconnected-(U$13-Pad08)") (class "Default")
      (node (ref "U$13") (pin "08") (pinfunction "08_08") (pintype "passive"))
    )
  )
)
